# LcsNodes-Building-Block-Generic-Power-Su.net
KiCad netlist of a schematic drawn in EasyEDA
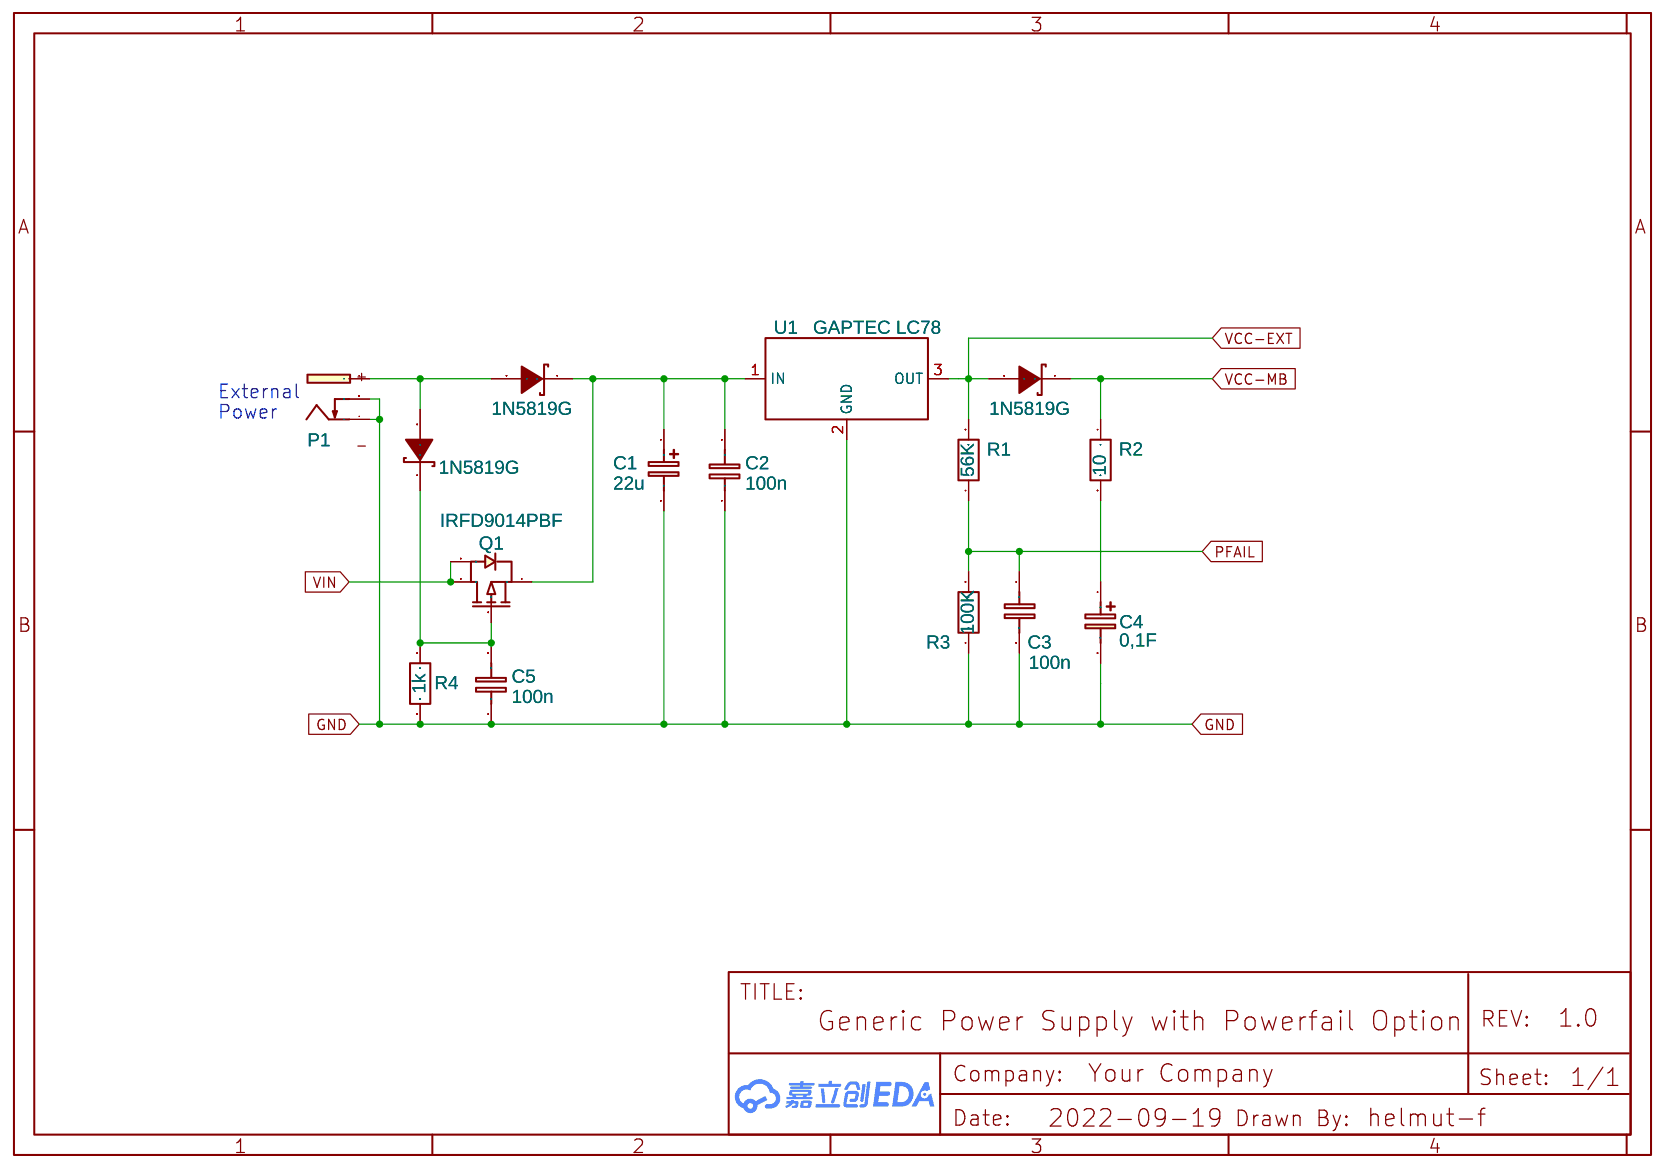
[diagram p0: schematic sheet]

(export (version "E")
  (design (tool "Eeschema 10.0.6"))
  (components
    (comp (ref "A1")
      (value "1N5819G")
      (fields (field (name "BOM_Supplier Part") "1N5819GOS-ND"))
      (libsource (lib "") (part "1N5819G"))
    )
    (comp (ref "A2")
      (value "1N5819G")
      (fields (field (name "BOM_Supplier Part") "1N5819GOS-ND"))
      (libsource (lib "") (part "1N5819G"))
    )
    (comp (ref "A3")
      (value "1N5819G")
      (fields (field (name "BOM_Supplier Part") "1N5819GOS-ND"))
      (libsource (lib "") (part "1N5819G_1"))
    )
    (comp (ref "C1") (value "22u") (libsource (lib "") (part "CE_TH_D4.0×F1.5_EU")))
    (comp (ref "C2") (value "100n") (libsource (lib "") (part "C_0603_EU")))
    (comp (ref "C3") (value "100n") (libsource (lib "") (part "C_RAD-0.2_EU")))
    (comp (ref "C4") (value "0,1F") (libsource (lib "") (part "C_Tan_SMD_A_EU")))
    (comp (ref "C5") (value "100n") (libsource (lib "") (part "C_0603_EU")))
    (comp (ref "P1") (value "External Power") (libsource (lib "") (part "DC21P")))
    (comp (ref "Q1")
      (value "IRFD9014PBF")
      (fields (field (name "BOM_Supplier Part") "C727522"))
      (libsource (lib "") (part "IRFD9014PBF"))
    )
    (comp (ref "R1") (value "56K") (libsource (lib "") (part "R_AXIAL-0.3_EU_1")))
    (comp (ref "R2") (value "10") (libsource (lib "") (part "R_AXIAL-0.3_EU")))
    (comp (ref "R3") (value "100K") (libsource (lib "") (part "R_AXIAL-0.3_EU_1")))
    (comp (ref "R4") (value "1k") (libsource (lib "") (part "R_AXIAL-0.3_EU")))
    (comp (ref "U1") (value "GAPTEC LC78") (libsource (lib "") (part "GAPTEC LC78")))
  )
  (nets
    (net (code "1") (name "GND") (class "Default")
      (node (ref "C1") (pin "2") (pinfunction "2_2") (pintype "unspecified"))
      (node (ref "C2") (pin "1") (pinfunction "1_1") (pintype "unspecified"))
      (node (ref "C3") (pin "2") (pinfunction "2_2") (pintype "unspecified"))
      (node (ref "C4") (pin "2") (pinfunction "2_2") (pintype "unspecified"))
      (node (ref "C5") (pin "1") (pinfunction "1_1") (pintype "unspecified"))
      (node (ref "P1") (pin "-") (pinfunction "-_-") (pintype "unspecified"))
      (node (ref "P1") (pin "C") (pinfunction "C_C") (pintype "unspecified"))
      (node (ref "R3") (pin "1") (pinfunction "1_1") (pintype "unspecified"))
      (node (ref "R4") (pin "2") (pinfunction "2_2") (pintype "unspecified"))
      (node (ref "U1") (pin "2") (pinfunction "GND_2") (pintype "unspecified"))
    )
    (net (code "2") (name "Net-(A1-A)") (class "Default")
      (node (ref "A1") (pin "2") (pinfunction "A_2") (pintype "unspecified"))
      (node (ref "A3") (pin "2") (pinfunction "A_2") (pintype "unspecified"))
      (node (ref "P1") (pin "+") (pinfunction "+_+") (pintype "unspecified"))
    )
    (net (code "3") (name "Net-(A1-K)") (class "Default")
      (node (ref "A1") (pin "1") (pinfunction "K_1") (pintype "unspecified"))
      (node (ref "C1") (pin "1") (pinfunction "1_1") (pintype "unspecified"))
      (node (ref "C2") (pin "2") (pinfunction "2_2") (pintype "unspecified"))
      (node (ref "Q1") (pin "4") (pinfunction "S_4") (pintype "unspecified"))
      (node (ref "U1") (pin "1") (pinfunction "IN_1") (pintype "unspecified"))
    )
    (net (code "4") (name "Net-(A3-K)") (class "Default")
      (node (ref "A3") (pin "1") (pinfunction "K_1") (pintype "unspecified"))
      (node (ref "C5") (pin "2") (pinfunction "2_2") (pintype "unspecified"))
      (node (ref "Q1") (pin "3") (pinfunction "G_3") (pintype "unspecified"))
      (node (ref "R4") (pin "1") (pinfunction "1_1") (pintype "unspecified"))
    )
    (net (code "5") (name "Net-(C4-Pad1)") (class "Default")
      (node (ref "C4") (pin "1") (pinfunction "1_1") (pintype "unspecified"))
      (node (ref "R2") (pin "2") (pinfunction "2_2") (pintype "unspecified"))
    )
    (net (code "6") (name "PFAIL") (class "Default")
      (node (ref "C3") (pin "1") (pinfunction "1_1") (pintype "unspecified"))
      (node (ref "R1") (pin "1") (pinfunction "1_1") (pintype "unspecified"))
      (node (ref "R3") (pin "2") (pinfunction "2_2") (pintype "unspecified"))
    )
    (net (code "7") (name "VCC-EXT") (class "Default")
      (node (ref "A2") (pin "2") (pinfunction "A_2") (pintype "unspecified"))
      (node (ref "R1") (pin "2") (pinfunction "2_2") (pintype "unspecified"))
      (node (ref "U1") (pin "3") (pinfunction "OUT_3") (pintype "unspecified"))
    )
    (net (code "8") (name "VCC-MB") (class "Default")
      (node (ref "A2") (pin "1") (pinfunction "K_1") (pintype "unspecified"))
      (node (ref "R2") (pin "1") (pinfunction "1_1") (pintype "unspecified"))
    )
    (net (code "9") (name "VIN") (class "Default")
      (node (ref "Q1") (pin "1") (pinfunction "D_1") (pintype "unspecified"))
      (node (ref "Q1") (pin "2") (pinfunction "D_2") (pintype "unspecified"))
    )
  )
)
